# MCU.net
KiCad netlist of a schematic drawn in Altium Designer
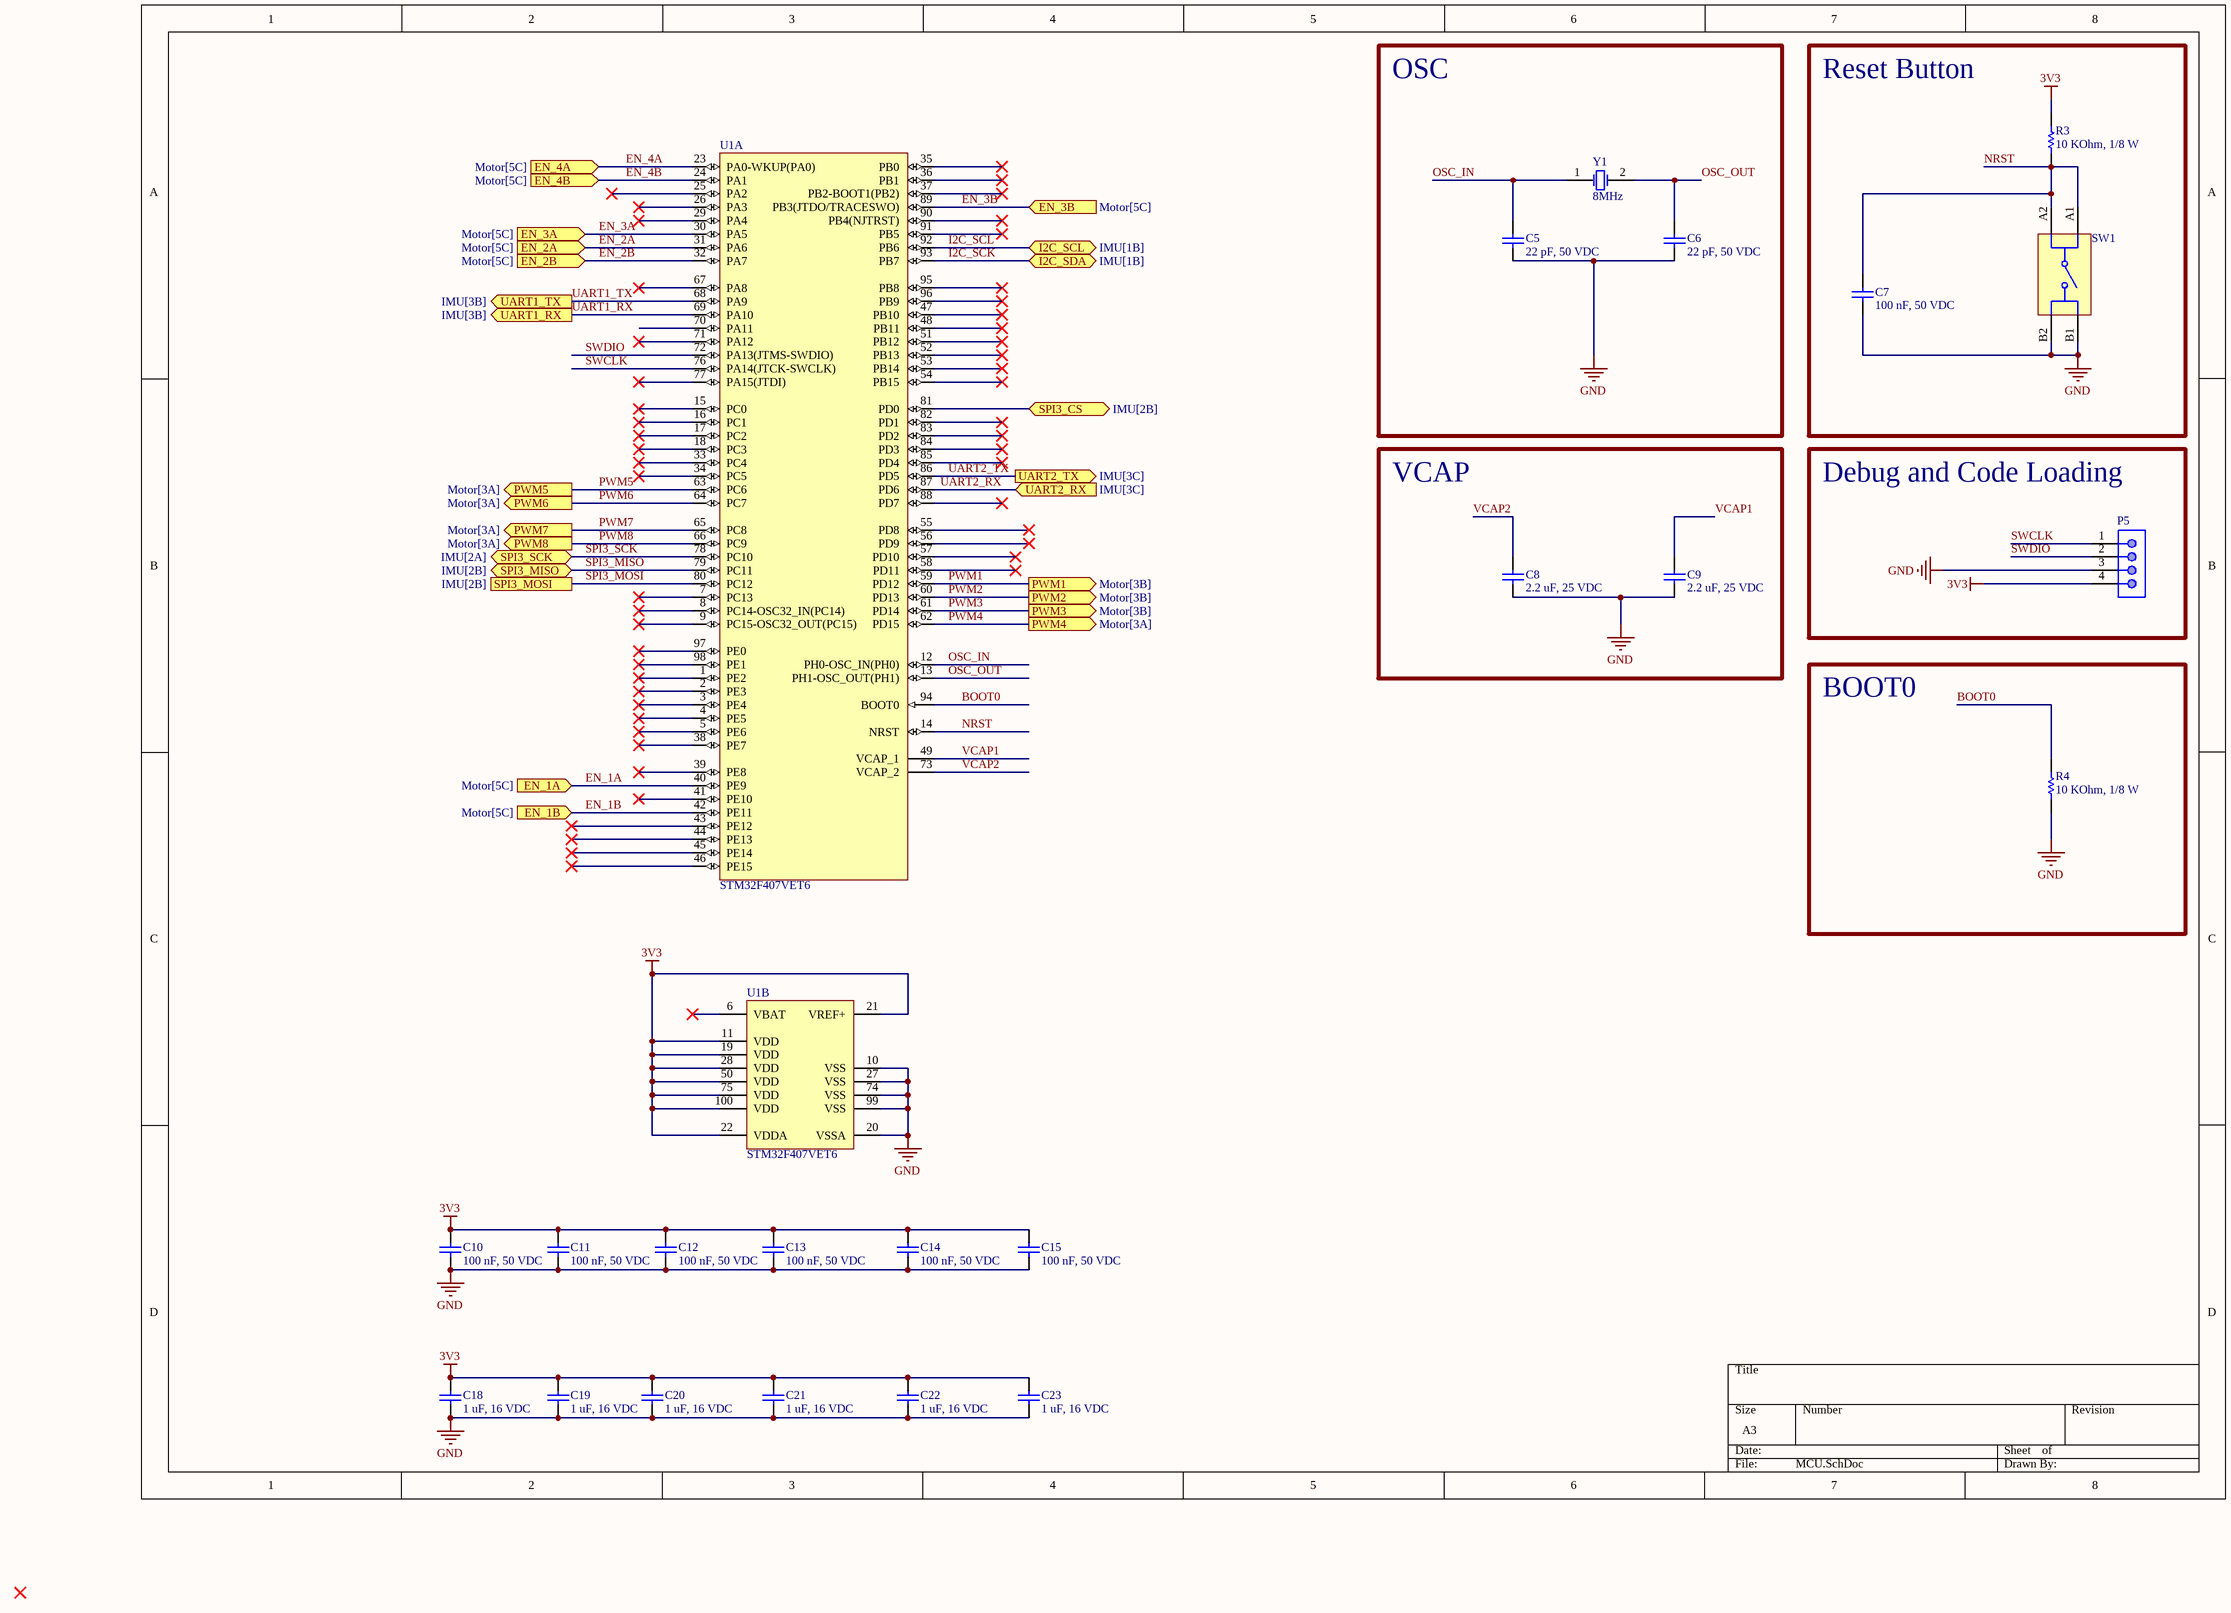
[diagram p0: MCU.SchDoc]

(export (version "E")
  (design (tool "Eeschema 10.0.6"))
  (components
    (comp (ref "C5")
      (value "22 pF, 50 VDC")
      (footprint "CAP_0805")
      (description "CAP, size 0805, 22 pF, 50 VDC")
      (fields (field (name "TOLERANCE") "+/-5%"))
      (libsource (lib "Altium_Ceramic_Cap") (part "0108052231050"))
    )
    (comp (ref "C6")
      (value "22 pF, 50 VDC")
      (footprint "CAP_0805")
      (description "CAP, size 0805, 22 pF, 50 VDC")
      (fields (field (name "TOLERANCE") "+/-5%"))
      (libsource (lib "Altium_Ceramic_Cap") (part "0108052231050"))
    )
    (comp (ref "C7")
      (value "100 nF, 50 VDC")
      (footprint "CAP_0805")
      (description "CAP, size 0805, 100 nF, 50 VDC")
      (fields (field (name "TOLERANCE") "+/-10%"))
      (libsource (lib "Altium_Ceramic_Cap") (part "0108051541050"))
    )
    (comp (ref "C8")
      (value "2.2 uF, 25 VDC")
      (footprint "CAP_0805")
      (description "CAP, size 0805, 2.2 uF, 25 VDC")
      (fields (field (name "TOLERANCE") "+/-10%"))
      (libsource (lib "Altium_Ceramic_Cap") (part "0108052251025"))
    )
    (comp (ref "C9")
      (value "2.2 uF, 25 VDC")
      (footprint "CAP_0805")
      (description "CAP, size 0805, 2.2 uF, 25 VDC")
      (fields (field (name "TOLERANCE") "+/-10%"))
      (libsource (lib "Altium_Ceramic_Cap") (part "0108052251025"))
    )
    (comp (ref "C10")
      (value "100 nF, 50 VDC")
      (footprint "CAP_0805")
      (description "CAP, size 0805, 100 nF, 50 VDC")
      (fields (field (name "TOLERANCE") "+/-5%"))
      (libsource (lib "Altium_Ceramic_Cap") (part "0108051031050"))
    )
    (comp (ref "C11")
      (value "100 nF, 50 VDC")
      (footprint "CAP_0805")
      (description "CAP, size 0805, 100 nF, 50 VDC")
      (fields (field (name "TOLERANCE") "+/-5%"))
      (libsource (lib "Altium_Ceramic_Cap") (part "0108051031050"))
    )
    (comp (ref "C12")
      (value "100 nF, 50 VDC")
      (footprint "CAP_0805")
      (description "CAP, size 0805, 100 nF, 50 VDC")
      (fields (field (name "TOLERANCE") "+/-5%"))
      (libsource (lib "Altium_Ceramic_Cap") (part "0108051031050"))
    )
    (comp (ref "C13")
      (value "100 nF, 50 VDC")
      (footprint "CAP_0805")
      (description "CAP, size 0805, 100 nF, 50 VDC")
      (fields (field (name "TOLERANCE") "+/-5%"))
      (libsource (lib "Altium_Ceramic_Cap") (part "0108051031050"))
    )
    (comp (ref "C14")
      (value "100 nF, 50 VDC")
      (footprint "CAP_0805")
      (description "CAP, size 0805, 100 nF, 50 VDC")
      (fields (field (name "TOLERANCE") "+/-5%"))
      (libsource (lib "Altium_Ceramic_Cap") (part "0108051031050"))
    )
    (comp (ref "C15")
      (value "100 nF, 50 VDC")
      (footprint "CAP_0805")
      (description "CAP, size 0805, 100 nF, 50 VDC")
      (fields (field (name "TOLERANCE") "+/-5%"))
      (libsource (lib "Altium_Ceramic_Cap") (part "0108051031050"))
    )
    (comp (ref "C18")
      (value "1 uF, 16 VDC")
      (footprint "CAP_0805")
      (description "CAP, size 0805, 1 uF, 16 VDC")
      (fields (field (name "TOLERANCE") "+/-10%"))
      (libsource (lib "Altium_Ceramic_Cap") (part "0108051051016"))
    )
    (comp (ref "C19")
      (value "1 uF, 16 VDC")
      (footprint "CAP_0805")
      (description "CAP, size 0805, 1 uF, 16 VDC")
      (fields (field (name "TOLERANCE") "+/-10%"))
      (libsource (lib "Altium_Ceramic_Cap") (part "0108051051016"))
    )
    (comp (ref "C20")
      (value "1 uF, 16 VDC")
      (footprint "CAP_0805")
      (description "CAP, size 0805, 1 uF, 16 VDC")
      (fields (field (name "TOLERANCE") "+/-10%"))
      (libsource (lib "Altium_Ceramic_Cap") (part "0108051051016"))
    )
    (comp (ref "C21")
      (value "1 uF, 16 VDC")
      (footprint "CAP_0805")
      (description "CAP, size 0805, 1 uF, 16 VDC")
      (fields (field (name "TOLERANCE") "+/-10%"))
      (libsource (lib "Altium_Ceramic_Cap") (part "0108051051016"))
    )
    (comp (ref "C22")
      (value "1 uF, 16 VDC")
      (footprint "CAP_0805")
      (description "CAP, size 0805, 1 uF, 16 VDC")
      (fields (field (name "TOLERANCE") "+/-10%"))
      (libsource (lib "Altium_Ceramic_Cap") (part "0108051051016"))
    )
    (comp (ref "C23")
      (value "1 uF, 16 VDC")
      (footprint "CAP_0805")
      (description "CAP, size 0805, 1 uF, 16 VDC")
      (fields (field (name "TOLERANCE") "+/-10%"))
      (libsource (lib "Altium_Ceramic_Cap") (part "0108051051016"))
    )
    (comp (ref "P5")
      (value "61300411121")
      (footprint "61300411121")
      (description "WR-PHD Pin Header, THT, pitch 2.54mm, Single Row, Vertical, 4p")
      (fields (field (name "MANUFACTURER") "Wurth Elektronik"))
      (libsource (lib "Altium_Header") (part "61300411121"))
    )
    (comp (ref "R3")
      (value "10 KOhm, 1/8 W")
      (footprint "RESISTOR_0805")
      (description "RES, size 0805, 10 KOhm, 1/8 W")
      (libsource (lib "Altium_Resistor") (part "0008051031"))
    )
    (comp (ref "R4")
      (value "10 KOhm, 1/8 W")
      (footprint "RESISTOR_0805")
      (description "RES, size 0805, 10 KOhm, 1/8 W")
      (libsource (lib "Altium_Resistor") (part "0008051031"))
    )
    (comp (ref "SW1")
      (value "430483035816")
      (footprint "WS-TASV_L6W6H3.5_4304x30358x6")
      (description "WS-TASV J-Bend SMT Washable Tact Switch, 12VDC, 50mA, 160g, height 3.5mm")
      (fields (field (name "MANUFACTURER") "Wurth Elektronik"))
      (libsource (lib "Board_C24") (part "430483035816"))
    )
    (comp (ref "U1")
      (value "STM32F407VET6")
      (footprint "STM-LQFP100_V")
      (fields (field (name "MANUFACTURER") "STMicroelectronics"))
      (libsource (lib "Altium Content Vault") (part "MC-ARM-STM32F40X_41X-SQ100"))
    )
    (comp (ref "Y1")
      (value "8MHz")
      (footprint "WE-XTAL_HC49/4HSMX")
      (description "WE-XTAL Quartz Crystal, SMT, HC49/4HSMX, 8MHz, +/-30ppm")
      (fields
        (field (name "MANUFACTURER PART NUMBER") "830003151")
        (field (name "MANUFACTURER") "Wurth Elektronik")
      )
      (libsource (lib "Altium_XTAL") (part "071105086016"))
    )
  )
  (nets
    (net (code "1") (name "/BOOT0") (class "Default")
      (node (ref "R4") (pin "2") (pinfunction "2_2") (pintype "passive"))
      (node (ref "U1") (pin "94") (pinfunction "BOOT0_94") (pintype "input"))
    )
    (net (code "2") (name "/EN_1A") (class "Default")
      (node (ref "U1") (pin "40") (pinfunction "PE9_40") (pintype "bidirectional"))
    )
    (net (code "3") (name "/EN_1B") (class "Default")
      (node (ref "U1") (pin "42") (pinfunction "PE11_42") (pintype "bidirectional"))
    )
    (net (code "4") (name "/EN_2A") (class "Default")
      (node (ref "U1") (pin "31") (pinfunction "PA6_31") (pintype "bidirectional"))
    )
    (net (code "5") (name "/EN_2B") (class "Default")
      (node (ref "U1") (pin "32") (pinfunction "PA7_32") (pintype "bidirectional"))
    )
    (net (code "6") (name "/EN_3A") (class "Default")
      (node (ref "U1") (pin "30") (pinfunction "PA5_30") (pintype "bidirectional"))
    )
    (net (code "7") (name "/EN_3B") (class "Default")
      (node (ref "U1") (pin "89") (pinfunction "PB3(JTDO/TRACESWO)_89") (pintype "bidirectional"))
    )
    (net (code "8") (name "/EN_4A") (class "Default")
      (node (ref "U1") (pin "23") (pinfunction "PA0-WKUP(PA0)_23") (pintype "bidirectional"))
    )
    (net (code "9") (name "/EN_4B") (class "Default")
      (node (ref "U1") (pin "24") (pinfunction "PA1_24") (pintype "bidirectional"))
    )
    (net (code "10") (name "/I2C_SCK") (class "Default")
      (node (ref "U1") (pin "93") (pinfunction "PB7_93") (pintype "bidirectional"))
    )
    (net (code "11") (name "/I2C_SCL") (class "Default")
      (node (ref "U1") (pin "92") (pinfunction "PB6_92") (pintype "bidirectional"))
    )
    (net (code "12") (name "/NRST") (class "Default")
      (node (ref "C7") (pin "2") (pinfunction "2_2") (pintype "passive"))
      (node (ref "R3") (pin "1") (pinfunction "1_1") (pintype "passive"))
      (node (ref "SW1") (pin "A1") (pinfunction "A1_A1") (pintype "passive"))
      (node (ref "SW1") (pin "A2") (pinfunction "A2_A2") (pintype "passive"))
      (node (ref "U1") (pin "14") (pinfunction "NRST_14") (pintype "bidirectional"))
    )
    (net (code "13") (name "/OSC_IN") (class "Default")
      (node (ref "C5") (pin "2") (pinfunction "2_2") (pintype "passive"))
      (node (ref "U1") (pin "12") (pinfunction "PH0-OSC_IN(PH0)_12") (pintype "bidirectional"))
      (node (ref "Y1") (pin "1") (pinfunction "OSC1_1") (pintype "passive"))
    )
    (net (code "14") (name "/OSC_OUT") (class "Default")
      (node (ref "C6") (pin "2") (pinfunction "2_2") (pintype "passive"))
      (node (ref "U1") (pin "13") (pinfunction "PH1-OSC_OUT(PH1)_13") (pintype "bidirectional"))
      (node (ref "Y1") (pin "2") (pinfunction "OSC2_2") (pintype "passive"))
    )
    (net (code "15") (name "/PWM1") (class "Default")
      (node (ref "U1") (pin "59") (pinfunction "PD12_59") (pintype "bidirectional"))
    )
    (net (code "16") (name "/PWM2") (class "Default")
      (node (ref "U1") (pin "60") (pinfunction "PD13_60") (pintype "bidirectional"))
    )
    (net (code "17") (name "/PWM3") (class "Default")
      (node (ref "U1") (pin "61") (pinfunction "PD14_61") (pintype "bidirectional"))
    )
    (net (code "18") (name "/PWM4") (class "Default")
      (node (ref "U1") (pin "62") (pinfunction "PD15_62") (pintype "bidirectional"))
    )
    (net (code "19") (name "/PWM5") (class "Default")
      (node (ref "U1") (pin "63") (pinfunction "PC6_63") (pintype "bidirectional"))
    )
    (net (code "20") (name "/PWM6") (class "Default")
      (node (ref "U1") (pin "64") (pinfunction "PC7_64") (pintype "bidirectional"))
    )
    (net (code "21") (name "/PWM7") (class "Default")
      (node (ref "U1") (pin "65") (pinfunction "PC8_65") (pintype "bidirectional"))
    )
    (net (code "22") (name "/PWM8") (class "Default")
      (node (ref "U1") (pin "66") (pinfunction "PC9_66") (pintype "bidirectional"))
    )
    (net (code "23") (name "/SPI3_CS") (class "Default")
      (node (ref "U1") (pin "81") (pinfunction "PD0_81") (pintype "bidirectional"))
    )
    (net (code "24") (name "/SPI3_MISO") (class "Default")
      (node (ref "U1") (pin "79") (pinfunction "PC11_79") (pintype "bidirectional"))
    )
    (net (code "25") (name "/SPI3_MOSI") (class "Default")
      (node (ref "U1") (pin "80") (pinfunction "PC12_80") (pintype "bidirectional"))
    )
    (net (code "26") (name "/SPI3_SCK") (class "Default")
      (node (ref "U1") (pin "78") (pinfunction "PC10_78") (pintype "bidirectional"))
    )
    (net (code "27") (name "/SWCLK") (class "Default")
      (node (ref "P5") (pin "1") (pinfunction "1_1") (pintype "passive"))
      (node (ref "U1") (pin "76") (pinfunction "PA14(JTCK-SWCLK)_76") (pintype "bidirectional"))
    )
    (net (code "28") (name "/SWDIO") (class "Default")
      (node (ref "P5") (pin "2") (pinfunction "2_2") (pintype "passive"))
      (node (ref "U1") (pin "72") (pinfunction "PA13(JTMS-SWDIO)_72") (pintype "bidirectional"))
    )
    (net (code "29") (name "/UART1_RX") (class "Default")
      (node (ref "U1") (pin "69") (pinfunction "PA10_69") (pintype "bidirectional"))
    )
    (net (code "30") (name "/UART1_TX") (class "Default")
      (node (ref "U1") (pin "68") (pinfunction "PA9_68") (pintype "bidirectional"))
    )
    (net (code "31") (name "/UART2_RX") (class "Default")
      (node (ref "U1") (pin "87") (pinfunction "PD6_87") (pintype "bidirectional"))
    )
    (net (code "32") (name "/UART2_TX") (class "Default")
      (node (ref "U1") (pin "86") (pinfunction "PD5_86") (pintype "bidirectional"))
    )
    (net (code "33") (name "/VCAP1") (class "Default")
      (node (ref "C9") (pin "2") (pinfunction "2_2") (pintype "passive"))
      (node (ref "U1") (pin "49") (pinfunction "VCAP_1_49") (pintype "power_in"))
    )
    (net (code "34") (name "/VCAP2") (class "Default")
      (node (ref "C8") (pin "2") (pinfunction "2_2") (pintype "passive"))
      (node (ref "U1") (pin "73") (pinfunction "VCAP_2_73") (pintype "power_in"))
    )
    (net (code "35") (name "3V3") (class "Default")
      (node (ref "C10") (pin "2") (pinfunction "2_2") (pintype "passive"))
      (node (ref "C11") (pin "2") (pinfunction "2_2") (pintype "passive"))
      (node (ref "C12") (pin "2") (pinfunction "2_2") (pintype "passive"))
      (node (ref "C13") (pin "2") (pinfunction "2_2") (pintype "passive"))
      (node (ref "C14") (pin "2") (pinfunction "2_2") (pintype "passive"))
      (node (ref "C15") (pin "2") (pinfunction "2_2") (pintype "passive"))
      (node (ref "C18") (pin "2") (pinfunction "2_2") (pintype "passive"))
      (node (ref "C19") (pin "2") (pinfunction "2_2") (pintype "passive"))
      (node (ref "C20") (pin "2") (pinfunction "2_2") (pintype "passive"))
      (node (ref "C21") (pin "2") (pinfunction "2_2") (pintype "passive"))
      (node (ref "C22") (pin "2") (pinfunction "2_2") (pintype "passive"))
      (node (ref "C23") (pin "2") (pinfunction "2_2") (pintype "passive"))
      (node (ref "P5") (pin "4") (pinfunction "4_4") (pintype "passive"))
      (node (ref "R3") (pin "2") (pinfunction "2_2") (pintype "passive"))
      (node (ref "U1") (pin "100") (pinfunction "VDD_100") (pintype "power_in"))
      (node (ref "U1") (pin "11") (pinfunction "VDD_11") (pintype "power_in"))
      (node (ref "U1") (pin "19") (pinfunction "VDD_19") (pintype "power_in"))
      (node (ref "U1") (pin "21") (pinfunction "VREF+_21") (pintype "power_in"))
      (node (ref "U1") (pin "22") (pinfunction "VDDA_22") (pintype "power_in"))
      (node (ref "U1") (pin "28") (pinfunction "VDD_28") (pintype "power_in"))
      (node (ref "U1") (pin "50") (pinfunction "VDD_50") (pintype "power_in"))
      (node (ref "U1") (pin "75") (pinfunction "VDD_75") (pintype "power_in"))
    )
    (net (code "36") (name "GND") (class "Default")
      (node (ref "C10") (pin "1") (pinfunction "1_1") (pintype "passive"))
      (node (ref "C11") (pin "1") (pinfunction "1_1") (pintype "passive"))
      (node (ref "C12") (pin "1") (pinfunction "1_1") (pintype "passive"))
      (node (ref "C13") (pin "1") (pinfunction "1_1") (pintype "passive"))
      (node (ref "C14") (pin "1") (pinfunction "1_1") (pintype "passive"))
      (node (ref "C15") (pin "1") (pinfunction "1_1") (pintype "passive"))
      (node (ref "C18") (pin "1") (pinfunction "1_1") (pintype "passive"))
      (node (ref "C19") (pin "1") (pinfunction "1_1") (pintype "passive"))
      (node (ref "C20") (pin "1") (pinfunction "1_1") (pintype "passive"))
      (node (ref "C21") (pin "1") (pinfunction "1_1") (pintype "passive"))
      (node (ref "C22") (pin "1") (pinfunction "1_1") (pintype "passive"))
      (node (ref "C23") (pin "1") (pinfunction "1_1") (pintype "passive"))
      (node (ref "C5") (pin "1") (pinfunction "1_1") (pintype "passive"))
      (node (ref "C6") (pin "1") (pinfunction "1_1") (pintype "passive"))
      (node (ref "C7") (pin "1") (pinfunction "1_1") (pintype "passive"))
      (node (ref "C8") (pin "1") (pinfunction "1_1") (pintype "passive"))
      (node (ref "C9") (pin "1") (pinfunction "1_1") (pintype "passive"))
      (node (ref "P5") (pin "3") (pinfunction "3_3") (pintype "passive"))
      (node (ref "R4") (pin "1") (pinfunction "1_1") (pintype "passive"))
      (node (ref "SW1") (pin "B1") (pinfunction "B1_B1") (pintype "passive"))
      (node (ref "SW1") (pin "B2") (pinfunction "B2_B2") (pintype "passive"))
      (node (ref "U1") (pin "10") (pinfunction "VSS_10") (pintype "power_in"))
      (node (ref "U1") (pin "20") (pinfunction "VSSA_20") (pintype "power_in"))
      (node (ref "U1") (pin "27") (pinfunction "VSS_27") (pintype "power_in"))
      (node (ref "U1") (pin "74") (pinfunction "VSS_74") (pintype "power_in"))
      (node (ref "U1") (pin "99") (pinfunction "VSS_99") (pintype "power_in"))
    )
    (net (code "37") (name "unconnected-(U1A-PA2-Pad25)") (class "Default")
      (node (ref "U1") (pin "25") (pinfunction "PA2_25") (pintype "bidirectional+no_connect"))
    )
    (net (code "38") (name "unconnected-(U1A-PA3-Pad26)") (class "Default")
      (node (ref "U1") (pin "26") (pinfunction "PA3_26") (pintype "bidirectional+no_connect"))
    )
    (net (code "39") (name "unconnected-(U1A-PA4-Pad29)") (class "Default")
      (node (ref "U1") (pin "29") (pinfunction "PA4_29") (pintype "bidirectional+no_connect"))
    )
    (net (code "40") (name "unconnected-(U1A-PA8-Pad67)") (class "Default")
      (node (ref "U1") (pin "67") (pinfunction "PA8_67") (pintype "bidirectional+no_connect"))
    )
    (net (code "41") (name "unconnected-(U1A-PA11-Pad70)") (class "Default")
      (node (ref "U1") (pin "70") (pinfunction "PA11_70") (pintype "bidirectional"))
    )
    (net (code "42") (name "unconnected-(U1A-PA12-Pad71)") (class "Default")
      (node (ref "U1") (pin "71") (pinfunction "PA12_71") (pintype "bidirectional+no_connect"))
    )
    (net (code "43") (name "unconnected-(U1A-PA15(JTDI)-Pad77)") (class "Default")
      (node (ref "U1") (pin "77") (pinfunction "PA15(JTDI)_77") (pintype "bidirectional+no_connect"))
    )
    (net (code "44") (name "unconnected-(U1A-PB0-Pad35)") (class "Default")
      (node (ref "U1") (pin "35") (pinfunction "PB0_35") (pintype "bidirectional+no_connect"))
    )
    (net (code "45") (name "unconnected-(U1A-PB1-Pad36)") (class "Default")
      (node (ref "U1") (pin "36") (pinfunction "PB1_36") (pintype "bidirectional+no_connect"))
    )
    (net (code "46") (name "unconnected-(U1A-PB2-BOOT1(PB2)-Pad37)") (class "Default")
      (node (ref "U1") (pin "37") (pinfunction "PB2-BOOT1(PB2)_37") (pintype "bidirectional+no_connect"))
    )
    (net (code "47") (name "unconnected-(U1A-PB4(NJTRST)-Pad90)") (class "Default")
      (node (ref "U1") (pin "90") (pinfunction "PB4(NJTRST)_90") (pintype "bidirectional+no_connect"))
    )
    (net (code "48") (name "unconnected-(U1A-PB5-Pad91)") (class "Default")
      (node (ref "U1") (pin "91") (pinfunction "PB5_91") (pintype "bidirectional+no_connect"))
    )
    (net (code "49") (name "unconnected-(U1A-PB8-Pad95)") (class "Default")
      (node (ref "U1") (pin "95") (pinfunction "PB8_95") (pintype "bidirectional+no_connect"))
    )
    (net (code "50") (name "unconnected-(U1A-PB9-Pad96)") (class "Default")
      (node (ref "U1") (pin "96") (pinfunction "PB9_96") (pintype "bidirectional+no_connect"))
    )
    (net (code "51") (name "unconnected-(U1A-PB10-Pad47)") (class "Default")
      (node (ref "U1") (pin "47") (pinfunction "PB10_47") (pintype "bidirectional+no_connect"))
    )
    (net (code "52") (name "unconnected-(U1A-PB11-Pad48)") (class "Default")
      (node (ref "U1") (pin "48") (pinfunction "PB11_48") (pintype "bidirectional+no_connect"))
    )
    (net (code "53") (name "unconnected-(U1A-PB12-Pad51)") (class "Default")
      (node (ref "U1") (pin "51") (pinfunction "PB12_51") (pintype "bidirectional+no_connect"))
    )
    (net (code "54") (name "unconnected-(U1A-PB13-Pad52)") (class "Default")
      (node (ref "U1") (pin "52") (pinfunction "PB13_52") (pintype "bidirectional+no_connect"))
    )
    (net (code "55") (name "unconnected-(U1A-PB14-Pad53)") (class "Default")
      (node (ref "U1") (pin "53") (pinfunction "PB14_53") (pintype "bidirectional+no_connect"))
    )
    (net (code "56") (name "unconnected-(U1A-PB15-Pad54)") (class "Default")
      (node (ref "U1") (pin "54") (pinfunction "PB15_54") (pintype "bidirectional+no_connect"))
    )
    (net (code "57") (name "unconnected-(U1A-PC0-Pad15)") (class "Default")
      (node (ref "U1") (pin "15") (pinfunction "PC0_15") (pintype "bidirectional+no_connect"))
    )
    (net (code "58") (name "unconnected-(U1A-PC1-Pad16)") (class "Default")
      (node (ref "U1") (pin "16") (pinfunction "PC1_16") (pintype "bidirectional+no_connect"))
    )
    (net (code "59") (name "unconnected-(U1A-PC2-Pad17)") (class "Default")
      (node (ref "U1") (pin "17") (pinfunction "PC2_17") (pintype "bidirectional+no_connect"))
    )
    (net (code "60") (name "unconnected-(U1A-PC3-Pad18)") (class "Default")
      (node (ref "U1") (pin "18") (pinfunction "PC3_18") (pintype "bidirectional+no_connect"))
    )
    (net (code "61") (name "unconnected-(U1A-PC4-Pad33)") (class "Default")
      (node (ref "U1") (pin "33") (pinfunction "PC4_33") (pintype "bidirectional+no_connect"))
    )
    (net (code "62") (name "unconnected-(U1A-PC5-Pad34)") (class "Default")
      (node (ref "U1") (pin "34") (pinfunction "PC5_34") (pintype "bidirectional+no_connect"))
    )
    (net (code "63") (name "unconnected-(U1A-PC13-Pad7)") (class "Default")
      (node (ref "U1") (pin "7") (pinfunction "PC13_7") (pintype "bidirectional+no_connect"))
    )
    (net (code "64") (name "unconnected-(U1A-PC14-OSC32_IN(PC14)-Pad8)") (class "Default")
      (node (ref "U1") (pin "8") (pinfunction "PC14-OSC32_IN(PC14)_8") (pintype "bidirectional+no_connect"))
    )
    (net (code "65") (name "unconnected-(U1A-PC15-OSC32_OUT(PC15)-Pad9)") (class "Default")
      (node (ref "U1") (pin "9") (pinfunction "PC15-OSC32_OUT(PC15)_9") (pintype "bidirectional+no_connect"))
    )
    (net (code "66") (name "unconnected-(U1A-PD1-Pad82)") (class "Default")
      (node (ref "U1") (pin "82") (pinfunction "PD1_82") (pintype "bidirectional+no_connect"))
    )
    (net (code "67") (name "unconnected-(U1A-PD2-Pad83)") (class "Default")
      (node (ref "U1") (pin "83") (pinfunction "PD2_83") (pintype "bidirectional+no_connect"))
    )
    (net (code "68") (name "unconnected-(U1A-PD3-Pad84)") (class "Default")
      (node (ref "U1") (pin "84") (pinfunction "PD3_84") (pintype "bidirectional+no_connect"))
    )
    (net (code "69") (name "unconnected-(U1A-PD4-Pad85)") (class "Default")
      (node (ref "U1") (pin "85") (pinfunction "PD4_85") (pintype "bidirectional+no_connect"))
    )
    (net (code "70") (name "unconnected-(U1A-PD7-Pad88)") (class "Default")
      (node (ref "U1") (pin "88") (pinfunction "PD7_88") (pintype "bidirectional+no_connect"))
    )
    (net (code "71") (name "unconnected-(U1A-PD8-Pad55)") (class "Default")
      (node (ref "U1") (pin "55") (pinfunction "PD8_55") (pintype "bidirectional+no_connect"))
    )
    (net (code "72") (name "unconnected-(U1A-PD9-Pad56)") (class "Default")
      (node (ref "U1") (pin "56") (pinfunction "PD9_56") (pintype "bidirectional+no_connect"))
    )
    (net (code "73") (name "unconnected-(U1A-PD10-Pad57)") (class "Default")
      (node (ref "U1") (pin "57") (pinfunction "PD10_57") (pintype "bidirectional+no_connect"))
    )
    (net (code "74") (name "unconnected-(U1A-PD11-Pad58)") (class "Default")
      (node (ref "U1") (pin "58") (pinfunction "PD11_58") (pintype "bidirectional+no_connect"))
    )
    (net (code "75") (name "unconnected-(U1A-PE0-Pad97)") (class "Default")
      (node (ref "U1") (pin "97") (pinfunction "PE0_97") (pintype "bidirectional+no_connect"))
    )
    (net (code "76") (name "unconnected-(U1A-PE1-Pad98)") (class "Default")
      (node (ref "U1") (pin "98") (pinfunction "PE1_98") (pintype "bidirectional+no_connect"))
    )
    (net (code "77") (name "unconnected-(U1A-PE2-Pad1)") (class "Default")
      (node (ref "U1") (pin "1") (pinfunction "PE2_1") (pintype "bidirectional+no_connect"))
    )
    (net (code "78") (name "unconnected-(U1A-PE3-Pad2)") (class "Default")
      (node (ref "U1") (pin "2") (pinfunction "PE3_2") (pintype "bidirectional+no_connect"))
    )
    (net (code "79") (name "unconnected-(U1A-PE4-Pad3)") (class "Default")
      (node (ref "U1") (pin "3") (pinfunction "PE4_3") (pintype "bidirectional+no_connect"))
    )
    (net (code "80") (name "unconnected-(U1A-PE5-Pad4)") (class "Default")
      (node (ref "U1") (pin "4") (pinfunction "PE5_4") (pintype "bidirectional+no_connect"))
    )
    (net (code "81") (name "unconnected-(U1A-PE6-Pad5)") (class "Default")
      (node (ref "U1") (pin "5") (pinfunction "PE6_5") (pintype "bidirectional+no_connect"))
    )
    (net (code "82") (name "unconnected-(U1A-PE7-Pad38)") (class "Default")
      (node (ref "U1") (pin "38") (pinfunction "PE7_38") (pintype "bidirectional+no_connect"))
    )
    (net (code "83") (name "unconnected-(U1A-PE8-Pad39)") (class "Default")
      (node (ref "U1") (pin "39") (pinfunction "PE8_39") (pintype "bidirectional+no_connect"))
    )
    (net (code "84") (name "unconnected-(U1A-PE10-Pad41)") (class "Default")
      (node (ref "U1") (pin "41") (pinfunction "PE10_41") (pintype "bidirectional+no_connect"))
    )
    (net (code "85") (name "unconnected-(U1A-PE12-Pad43)") (class "Default")
      (node (ref "U1") (pin "43") (pinfunction "PE12_43") (pintype "bidirectional+no_connect"))
    )
    (net (code "86") (name "unconnected-(U1A-PE13-Pad44)") (class "Default")
      (node (ref "U1") (pin "44") (pinfunction "PE13_44") (pintype "bidirectional+no_connect"))
    )
    (net (code "87") (name "unconnected-(U1A-PE14-Pad45)") (class "Default")
      (node (ref "U1") (pin "45") (pinfunction "PE14_45") (pintype "bidirectional+no_connect"))
    )
    (net (code "88") (name "unconnected-(U1A-PE15-Pad46)") (class "Default")
      (node (ref "U1") (pin "46") (pinfunction "PE15_46") (pintype "bidirectional+no_connect"))
    )
    (net (code "89") (name "unconnected-(U1B-VBAT-Pad6)") (class "Default")
      (node (ref "U1") (pin "6") (pinfunction "VBAT_6") (pintype "power_in+no_connect"))
    )
  )
)
